# switch.net
KiCad netlist of a schematic drawn in EAGLE
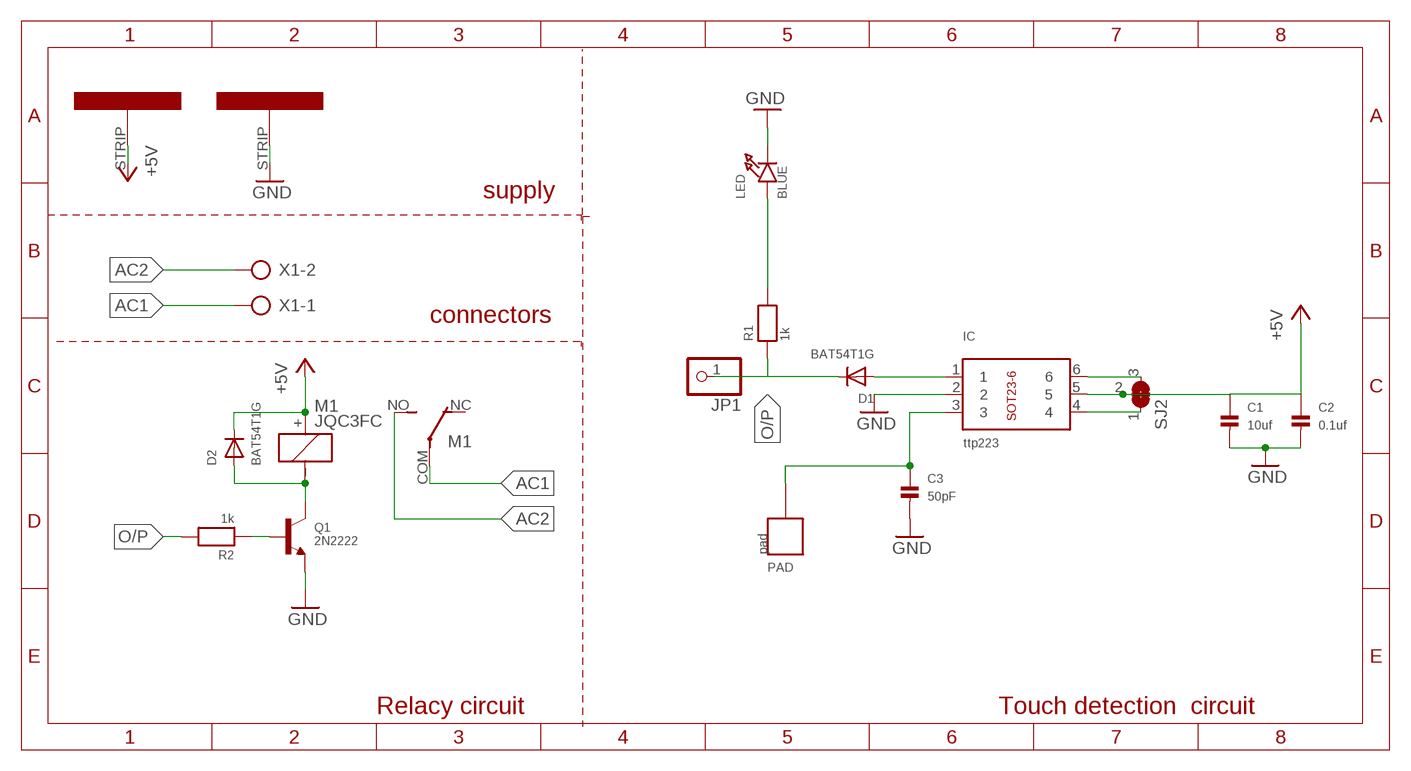
[diagram p0: schematic, sheet 1]

(export (version "E")
  (design (tool "Eeschema 10.0.6"))
  (components
    (comp (ref "C1")
      (value "10uf")
      (footprint "eagle-import:0805")
      (libsource (lib "eagle-import") (part "CAP_CERAMIC0805"))
    )
    (comp (ref "C2")
      (value "0.1uf")
      (footprint "eagle-import:0805")
      (libsource (lib "eagle-import") (part "CAP_CERAMIC0805"))
    )
    (comp (ref "C3")
      (value "50pF")
      (footprint "eagle-import:0805")
      (libsource (lib "eagle-import") (part "CAP_CERAMIC0805"))
    )
    (comp (ref "D1")
      (value "BAT54T1G")
      (footprint "eagle-import:SOD-123")
      (libsource (lib "eagle-import") (part "DIODESOD-123"))
    )
    (comp (ref "D2")
      (value "BAT54T1G")
      (footprint "eagle-import:SOD-123")
      (libsource (lib "eagle-import") (part "DIODESOD-123"))
    )
    (comp (ref "IC")
      (value "ttp223")
      (footprint "eagle-import:BREAKOUT_SOT23-6")
      (libsource (lib "eagle-import") (part "BREAKOUT_SOT23-6"))
    )
    (comp (ref "JP1")
      (value "HEADER-1X12MM")
      (footprint "eagle-import:1X01_2MM")
      (libsource (lib "eagle-import") (part "HEADER-1X12MM"))
    )
    (comp (ref "LED")
      (value "BLUE")
      (footprint "eagle-import:CHIPLED_0805")
      (libsource (lib "eagle-import") (part "LED0805"))
    )
    (comp (ref "M1")
      (value "JQC3FC")
      (footprint "eagle-import:JQC3FC")
      (libsource (lib "eagle-import") (part "JQC3FC"))
    )
    (comp (ref "PAD")
      (value "pad")
      (footprint "eagle-import:CAP_TOUCHPAD")
      (libsource (lib "eagle-import") (part "CAP_TOUCHPAD"))
    )
    (comp (ref "Q1")
      (value "2N2222")
      (footprint "eagle-import:SOT23-W")
      (libsource (lib "eagle-import") (part "TRANSISTOR_NPNWAVE"))
    )
    (comp (ref "R1")
      (value "1k")
      (footprint "eagle-import:0805")
      (libsource (lib "eagle-import") (part "RESISTOR0805"))
    )
    (comp (ref "R2")
      (value "1k")
      (footprint "eagle-import:0805")
      (libsource (lib "eagle-import") (part "RESISTOR0805"))
    )
    (comp (ref "RAIL1")
      (value "RAIL1")
      (footprint "eagle-import:STRIP")
      (libsource (lib "eagle-import") (part "STRIP"))
    )
    (comp (ref "RAIL2")
      (value "RAIL2")
      (footprint "eagle-import:STRIP")
      (libsource (lib "eagle-import") (part "STRIP"))
    )
    (comp (ref "SJ2")
      (value "SOLDERJUMPER_2WAY0603")
      (footprint "eagle-import:SOLDERJUMPER_2WAY_OPEN_0603")
      (libsource (lib "eagle-import") (part "SOLDERJUMPER_2WAY0603"))
    )
    (comp (ref "X1")
      (value "AK500/2-H")
      (footprint "eagle-import:AK500_2-H")
      (libsource (lib "eagle-import") (part "AK500/2-H"))
    )
  )
  (nets
    (net (code "1") (name "+5V") (class "Default")
      (node (ref "C1") (pin "1") (pinfunction "P$1_1") (pintype "passive"))
      (node (ref "C2") (pin "1") (pinfunction "P$1_1") (pintype "passive"))
      (node (ref "D2") (pin "C") (pinfunction "C_C") (pintype "passive"))
      (node (ref "IC") (pin "5") (pinfunction "5_5") (pintype "bidirectional"))
      (node (ref "M1") (pin "+") (pinfunction "+_+") (pintype "passive"))
      (node (ref "RAIL1") (pin "STRIP") (pinfunction "STRIP_STRIP") (pintype "bidirectional"))
      (node (ref "SJ2") (pin "2") (pinfunction "2_2") (pintype "passive"))
    )
    (net (code "2") (name "AC1") (class "Default")
      (node (ref "M1") (pin "COM") (pinfunction "COM_COM") (pintype "passive"))
      (node (ref "X1") (pin "1") (pinfunction "KL_1") (pintype "passive"))
    )
    (net (code "3") (name "AC2") (class "Default")
      (node (ref "M1") (pin "NO") (pinfunction "NO_NO") (pintype "passive"))
      (node (ref "X1") (pin "2") (pinfunction "KL_2") (pintype "passive"))
    )
    (net (code "4") (name "GND") (class "Default")
      (node (ref "C1") (pin "2") (pinfunction "P$2_2") (pintype "passive"))
      (node (ref "C2") (pin "2") (pinfunction "P$2_2") (pintype "passive"))
      (node (ref "C3") (pin "2") (pinfunction "P$2_2") (pintype "passive"))
      (node (ref "IC") (pin "2") (pinfunction "2_2") (pintype "bidirectional"))
      (node (ref "LED") (pin "C") (pinfunction "C_C") (pintype "passive"))
      (node (ref "Q1") (pin "2") (pinfunction "E_2") (pintype "passive"))
      (node (ref "RAIL2") (pin "STRIP") (pinfunction "STRIP_STRIP") (pintype "bidirectional"))
    )
    (net (code "5") (name "Net-(C3-P$1)") (class "Default")
      (node (ref "C3") (pin "1") (pinfunction "P$1_1") (pintype "passive"))
      (node (ref "IC") (pin "3") (pinfunction "3_3") (pintype "bidirectional"))
      (node (ref "PAD") (pin "P$1") (pinfunction "P$1_P$1") (pintype "bidirectional"))
    )
    (net (code "6") (name "Net-(D1-PadA)") (class "Default")
      (node (ref "D1") (pin "A") (pinfunction "A_A") (pintype "passive"))
      (node (ref "IC") (pin "1") (pinfunction "1_1") (pintype "bidirectional"))
    )
    (net (code "7") (name "Net-(IC-Pad4)") (class "Default")
      (node (ref "IC") (pin "4") (pinfunction "4_4") (pintype "bidirectional"))
      (node (ref "SJ2") (pin "1") (pinfunction "1_1") (pintype "passive"))
    )
    (net (code "8") (name "Net-(IC-Pad6)") (class "Default")
      (node (ref "IC") (pin "6") (pinfunction "6_6") (pintype "bidirectional"))
      (node (ref "SJ2") (pin "3") (pinfunction "3_3") (pintype "passive"))
    )
    (net (code "9") (name "Net-(LED-PadA)") (class "Default")
      (node (ref "LED") (pin "A") (pinfunction "A_A") (pintype "passive"))
      (node (ref "R1") (pin "2") (pinfunction "2_2") (pintype "passive"))
    )
    (net (code "10") (name "Net-(M1--)") (class "Default")
      (node (ref "D2") (pin "A") (pinfunction "A_A") (pintype "passive"))
      (node (ref "M1") (pin "_") (pinfunction "-__") (pintype "passive"))
      (node (ref "Q1") (pin "3") (pinfunction "C_3") (pintype "passive"))
    )
    (net (code "11") (name "Net-(Q1-B)") (class "Default")
      (node (ref "Q1") (pin "1") (pinfunction "B_1") (pintype "passive"))
      (node (ref "R2") (pin "1") (pinfunction "1_1") (pintype "passive"))
    )
    (net (code "12") (name "O{slash}P") (class "Default")
      (node (ref "D1") (pin "C") (pinfunction "C_C") (pintype "passive"))
      (node (ref "JP1") (pin "1") (pinfunction "1_1") (pintype "passive"))
      (node (ref "R1") (pin "1") (pinfunction "1_1") (pintype "passive"))
      (node (ref "R2") (pin "2") (pinfunction "2_2") (pintype "passive"))
    )
    (net (code "13") (name "unconnected-(M1-PadNC)") (class "Default")
      (node (ref "M1") (pin "NC") (pinfunction "NC_NC") (pintype "passive"))
    )
  )
)
